# power-module.net
KiCad netlist of a schematic drawn in EAGLE
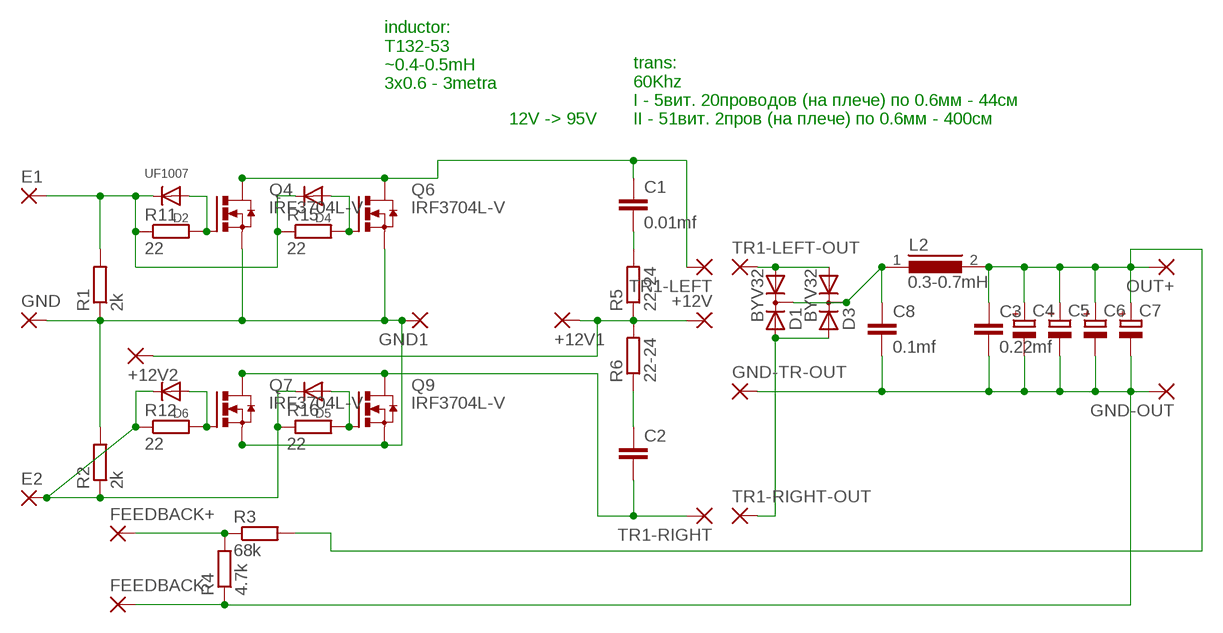
[diagram p0: schematic, sheet 1]

(export (version "E")
  (design (tool "Eeschema 10.0.6"))
  (components
    (comp (ref "+12V")
      (value "3,81/1,1")
      (footprint "eagle-import:3,81_1,1")
      (libsource (lib "eagle-import") (part "3,81/1,1"))
    )
    (comp (ref "+12V1")
      (value "3,81/1,1")
      (footprint "eagle-import:3,81_1,1")
      (libsource (lib "eagle-import") (part "3,81/1,1"))
    )
    (comp (ref "+12V2")
      (value "3,81/1,1")
      (footprint "eagle-import:3,81_1,1")
      (libsource (lib "eagle-import") (part "3,81/1,1"))
    )
    (comp (ref "C1")
      (value "0.01mf")
      (footprint "eagle-import:C102-064X133")
      (libsource (lib "eagle-import") (part "C-EU102-064X133"))
    )
    (comp (ref "C2")
      (value "C-EU102-064X133")
      (footprint "eagle-import:C102-064X133")
      (libsource (lib "eagle-import") (part "C-EU102-064X133"))
    )
    (comp (ref "C3")
      (value "0.22mf")
      (footprint "eagle-import:C150-064X183")
      (libsource (lib "eagle-import") (part "C-EU150-064X183"))
    )
    (comp (ref "C4")
      (value "CPOL-EUE10-22.5")
      (footprint "eagle-import:EB22,5D")
      (libsource (lib "eagle-import") (part "CPOL-EUE10-22.5"))
    )
    (comp (ref "C5")
      (value "CPOL-EUE10-22.5")
      (footprint "eagle-import:EB22,5D")
      (libsource (lib "eagle-import") (part "CPOL-EUE10-22.5"))
    )
    (comp (ref "C6")
      (value "CPOL-EUE10-22.5")
      (footprint "eagle-import:EB22,5D")
      (libsource (lib "eagle-import") (part "CPOL-EUE10-22.5"))
    )
    (comp (ref "C7")
      (value "CPOL-EUE10-22.5")
      (footprint "eagle-import:EB22,5D")
      (libsource (lib "eagle-import") (part "CPOL-EUE10-22.5"))
    )
    (comp (ref "C8")
      (value "0.1mf")
      (footprint "eagle-import:C150-064X183")
      (libsource (lib "eagle-import") (part "C-EU150-064X183"))
    )
    (comp (ref "D1")
      (value "BYV32")
      (footprint "eagle-import:TO220ABS")
      (libsource (lib "eagle-import") (part "BYV32"))
    )
    (comp (ref "D2")
      (value "UF1007")
      (footprint "eagle-import:DO-1N4148")
      (libsource (lib "eagle-import") (part "DIODEDO-1N4148"))
    )
    (comp (ref "D3")
      (value "BYV32")
      (footprint "eagle-import:TO220ABS")
      (libsource (lib "eagle-import") (part "BYV32"))
    )
    (comp (ref "D4")
      (value "DIODEDO-1N4148")
      (footprint "eagle-import:DO-1N4148")
      (libsource (lib "eagle-import") (part "DIODEDO-1N4148"))
    )
    (comp (ref "D5")
      (value "DIODEDO-1N4148")
      (footprint "eagle-import:DO-1N4148")
      (libsource (lib "eagle-import") (part "DIODEDO-1N4148"))
    )
    (comp (ref "D6")
      (value "DIODEDO-1N4148")
      (footprint "eagle-import:DO-1N4148")
      (libsource (lib "eagle-import") (part "DIODEDO-1N4148"))
    )
    (comp (ref "E1")
      (value "3,81/1,1")
      (footprint "eagle-import:3,81_1,1")
      (libsource (lib "eagle-import") (part "3,81/1,1"))
    )
    (comp (ref "E2")
      (value "3,81/1,1")
      (footprint "eagle-import:3,81_1,1")
      (libsource (lib "eagle-import") (part "3,81/1,1"))
    )
    (comp (ref "FEEDBACK+")
      (value "3,81/1,1")
      (footprint "eagle-import:3,81_1,1")
      (libsource (lib "eagle-import") (part "3,81/1,1"))
    )
    (comp (ref "FEEDBACK-")
      (value "3,81/1,1")
      (footprint "eagle-import:3,81_1,1")
      (libsource (lib "eagle-import") (part "3,81/1,1"))
    )
    (comp (ref "GND")
      (value "3,81/1,1")
      (footprint "eagle-import:3,81_1,1")
      (libsource (lib "eagle-import") (part "3,81/1,1"))
    )
    (comp (ref "GND-OUT")
      (value "3,81/1,1")
      (footprint "eagle-import:3,81_1,1")
      (libsource (lib "eagle-import") (part "3,81/1,1"))
    )
    (comp (ref "GND-TR-OUT")
      (value "3,81/1,1")
      (footprint "eagle-import:3,81_1,1")
      (libsource (lib "eagle-import") (part "3,81/1,1"))
    )
    (comp (ref "GND1")
      (value "3,81/1,1")
      (footprint "eagle-import:3,81_1,1")
      (libsource (lib "eagle-import") (part "3,81/1,1"))
    )
    (comp (ref "L2")
      (value "0.3-0.7mH")
      (footprint "eagle-import:11-27")
      (libsource (lib "eagle-import") (part "R2711F11"))
    )
    (comp (ref "OUT+")
      (value "3,81/1,1")
      (footprint "eagle-import:3,81_1,1")
      (libsource (lib "eagle-import") (part "3,81/1,1"))
    )
    (comp (ref "Q4")
      (value "IRF3704L-V")
      (footprint "eagle-import:TO262-V")
      (libsource (lib "eagle-import") (part "IRF3704L-V"))
    )
    (comp (ref "Q6")
      (value "IRF3704L-V")
      (footprint "eagle-import:TO262-V")
      (libsource (lib "eagle-import") (part "IRF3704L-V"))
    )
    (comp (ref "Q7")
      (value "IRF3704L-V")
      (footprint "eagle-import:TO262-V")
      (libsource (lib "eagle-import") (part "IRF3704L-V"))
    )
    (comp (ref "Q9")
      (value "IRF3704L-V")
      (footprint "eagle-import:TO262-V")
      (libsource (lib "eagle-import") (part "IRF3704L-V"))
    )
    (comp (ref "R1")
      (value "2k")
      (footprint "eagle-import:0204_7")
      (libsource (lib "eagle-import") (part "R-EU_0204/7"))
    )
    (comp (ref "R2")
      (value "2k")
      (footprint "eagle-import:0204_7")
      (libsource (lib "eagle-import") (part "R-EU_0204/7"))
    )
    (comp (ref "R3")
      (value "68k")
      (footprint "eagle-import:0617_17")
      (libsource (lib "eagle-import") (part "R-EU_0617/17"))
    )
    (comp (ref "R4")
      (value "4.7k")
      (footprint "eagle-import:0617_17")
      (libsource (lib "eagle-import") (part "R-EU_0617/17"))
    )
    (comp (ref "R5")
      (value "22-24")
      (footprint "eagle-import:P0613_15")
      (libsource (lib "eagle-import") (part "R-EU_0613/15"))
    )
    (comp (ref "R6")
      (value "22-24")
      (footprint "eagle-import:P0613_15")
      (libsource (lib "eagle-import") (part "R-EU_0613/15"))
    )
    (comp (ref "R11")
      (value "22")
      (footprint "eagle-import:0204_7")
      (libsource (lib "eagle-import") (part "R-EU_0204/7"))
    )
    (comp (ref "R12")
      (value "22")
      (footprint "eagle-import:0204_7")
      (libsource (lib "eagle-import") (part "R-EU_0204/7"))
    )
    (comp (ref "R15")
      (value "22")
      (footprint "eagle-import:0204_7")
      (libsource (lib "eagle-import") (part "R-EU_0204/7"))
    )
    (comp (ref "R16")
      (value "22")
      (footprint "eagle-import:0204_7")
      (libsource (lib "eagle-import") (part "R-EU_0204/7"))
    )
    (comp (ref "TR1-LEFT")
      (value "3,81/1,1")
      (footprint "eagle-import:3,81_1,1")
      (libsource (lib "eagle-import") (part "3,81/1,1"))
    )
    (comp (ref "TR1-LEFT-OUT")
      (value "3,81/1,1")
      (footprint "eagle-import:3,81_1,1")
      (libsource (lib "eagle-import") (part "3,81/1,1"))
    )
    (comp (ref "TR1-RIGHT")
      (value "3,81/1,1")
      (footprint "eagle-import:3,81_1,1")
      (libsource (lib "eagle-import") (part "3,81/1,1"))
    )
    (comp (ref "TR1-RIGHT-OUT")
      (value "3,81/1,1")
      (footprint "eagle-import:3,81_1,1")
      (libsource (lib "eagle-import") (part "3,81/1,1"))
    )
  )
  (nets
    (net (code "1") (name "Net-(+12V-P)") (class "Default")
      (node (ref "+12V") (pin "1") (pinfunction "P_1") (pintype "passive"))
      (node (ref "+12V1") (pin "1") (pinfunction "P_1") (pintype "passive"))
      (node (ref "+12V2") (pin "1") (pinfunction "P_1") (pintype "passive"))
      (node (ref "R5") (pin "1") (pinfunction "1_1") (pintype "passive"))
      (node (ref "R6") (pin "2") (pinfunction "2_2") (pintype "passive"))
    )
    (net (code "2") (name "Net-(C1-Pad2)") (class "Default")
      (node (ref "C1") (pin "2") (pinfunction "2_2") (pintype "passive"))
      (node (ref "R5") (pin "2") (pinfunction "2_2") (pintype "passive"))
    )
    (net (code "3") (name "Net-(C2-Pad1)") (class "Default")
      (node (ref "C2") (pin "1") (pinfunction "1_1") (pintype "passive"))
      (node (ref "R6") (pin "1") (pinfunction "1_1") (pintype "passive"))
    )
    (net (code "4") (name "Net-(C8-Pad1)") (class "Default")
      (node (ref "C8") (pin "1") (pinfunction "1_1") (pintype "passive"))
      (node (ref "D1") (pin "C") (pinfunction "C_C") (pintype "passive"))
      (node (ref "D3") (pin "C") (pinfunction "C_C") (pintype "passive"))
      (node (ref "L2") (pin "1") (pinfunction "1_1") (pintype "passive"))
    )
    (net (code "5") (name "Net-(E1-P)") (class "Default")
      (node (ref "D2") (pin "C") (pinfunction "C_C") (pintype "passive"))
      (node (ref "D4") (pin "C") (pinfunction "C_C") (pintype "passive"))
      (node (ref "E1") (pin "1") (pinfunction "P_1") (pintype "passive"))
      (node (ref "R1") (pin "2") (pinfunction "2_2") (pintype "passive"))
      (node (ref "R11") (pin "1") (pinfunction "1_1") (pintype "passive"))
      (node (ref "R15") (pin "1") (pinfunction "1_1") (pintype "passive"))
    )
    (net (code "6") (name "Net-(E2-P)") (class "Default")
      (node (ref "D5") (pin "C") (pinfunction "C_C") (pintype "passive"))
      (node (ref "D6") (pin "C") (pinfunction "C_C") (pintype "passive"))
      (node (ref "E2") (pin "1") (pinfunction "P_1") (pintype "passive"))
      (node (ref "R12") (pin "1") (pinfunction "1_1") (pintype "passive"))
      (node (ref "R16") (pin "1") (pinfunction "1_1") (pintype "passive"))
      (node (ref "R2") (pin "1") (pinfunction "1_1") (pintype "passive"))
    )
    (net (code "7") (name "Net-(FEEDBACK+-P)") (class "Default")
      (node (ref "FEEDBACK+") (pin "1") (pinfunction "P_1") (pintype "passive"))
      (node (ref "R3") (pin "1") (pinfunction "1_1") (pintype "passive"))
      (node (ref "R4") (pin "2") (pinfunction "2_2") (pintype "passive"))
    )
    (net (code "8") (name "Net-(FEEDBACK--P)") (class "Default")
      (node (ref "C3") (pin "2") (pinfunction "2_2") (pintype "passive"))
      (node (ref "C4") (pin "-") (pinfunction "-_-") (pintype "passive"))
      (node (ref "C5") (pin "-") (pinfunction "-_-") (pintype "passive"))
      (node (ref "C6") (pin "-") (pinfunction "-_-") (pintype "passive"))
      (node (ref "C7") (pin "-") (pinfunction "-_-") (pintype "passive"))
      (node (ref "C8") (pin "2") (pinfunction "2_2") (pintype "passive"))
      (node (ref "FEEDBACK-") (pin "1") (pinfunction "P_1") (pintype "passive"))
      (node (ref "GND-OUT") (pin "1") (pinfunction "P_1") (pintype "passive"))
      (node (ref "GND-TR-OUT") (pin "1") (pinfunction "P_1") (pintype "passive"))
      (node (ref "R4") (pin "1") (pinfunction "1_1") (pintype "passive"))
    )
    (net (code "9") (name "Net-(GND-P)") (class "Default")
      (node (ref "GND") (pin "1") (pinfunction "P_1") (pintype "passive"))
      (node (ref "GND1") (pin "1") (pinfunction "P_1") (pintype "passive"))
      (node (ref "Q4") (pin "3") (pinfunction "S_3") (pintype "passive"))
      (node (ref "Q6") (pin "3") (pinfunction "S_3") (pintype "passive"))
      (node (ref "Q7") (pin "3") (pinfunction "S_3") (pintype "passive"))
      (node (ref "Q9") (pin "3") (pinfunction "S_3") (pintype "passive"))
      (node (ref "R1") (pin "1") (pinfunction "1_1") (pintype "passive"))
      (node (ref "R2") (pin "2") (pinfunction "2_2") (pintype "passive"))
    )
    (net (code "10") (name "Net-(OUT+-P)") (class "Default")
      (node (ref "C3") (pin "1") (pinfunction "1_1") (pintype "passive"))
      (node (ref "C4") (pin "+") (pinfunction "+_+") (pintype "passive"))
      (node (ref "C5") (pin "+") (pinfunction "+_+") (pintype "passive"))
      (node (ref "C6") (pin "+") (pinfunction "+_+") (pintype "passive"))
      (node (ref "C7") (pin "+") (pinfunction "+_+") (pintype "passive"))
      (node (ref "L2") (pin "2") (pinfunction "2_2") (pintype "passive"))
      (node (ref "OUT+") (pin "1") (pinfunction "P_1") (pintype "passive"))
      (node (ref "R3") (pin "2") (pinfunction "2_2") (pintype "passive"))
    )
    (net (code "11") (name "Net-(Q4-D)") (class "Default")
      (node (ref "C1") (pin "1") (pinfunction "1_1") (pintype "passive"))
      (node (ref "Q4") (pin "2") (pinfunction "D_2") (pintype "passive"))
      (node (ref "Q6") (pin "2") (pinfunction "D_2") (pintype "passive"))
      (node (ref "TR1-LEFT") (pin "1") (pinfunction "P_1") (pintype "passive"))
    )
    (net (code "12") (name "Net-(Q4-G)") (class "Default")
      (node (ref "D2") (pin "A") (pinfunction "A_A") (pintype "passive"))
      (node (ref "Q4") (pin "1") (pinfunction "G_1") (pintype "passive"))
      (node (ref "R11") (pin "2") (pinfunction "2_2") (pintype "passive"))
    )
    (net (code "13") (name "Net-(Q6-G)") (class "Default")
      (node (ref "D4") (pin "A") (pinfunction "A_A") (pintype "passive"))
      (node (ref "Q6") (pin "1") (pinfunction "G_1") (pintype "passive"))
      (node (ref "R15") (pin "2") (pinfunction "2_2") (pintype "passive"))
    )
    (net (code "14") (name "Net-(Q7-D)") (class "Default")
      (node (ref "C2") (pin "2") (pinfunction "2_2") (pintype "passive"))
      (node (ref "Q7") (pin "2") (pinfunction "D_2") (pintype "passive"))
      (node (ref "Q9") (pin "2") (pinfunction "D_2") (pintype "passive"))
      (node (ref "TR1-RIGHT") (pin "1") (pinfunction "P_1") (pintype "passive"))
    )
    (net (code "15") (name "Net-(Q7-G)") (class "Default")
      (node (ref "D6") (pin "A") (pinfunction "A_A") (pintype "passive"))
      (node (ref "Q7") (pin "1") (pinfunction "G_1") (pintype "passive"))
      (node (ref "R12") (pin "2") (pinfunction "2_2") (pintype "passive"))
    )
    (net (code "16") (name "Net-(Q9-G)") (class "Default")
      (node (ref "D5") (pin "A") (pinfunction "A_A") (pintype "passive"))
      (node (ref "Q9") (pin "1") (pinfunction "G_1") (pintype "passive"))
      (node (ref "R16") (pin "2") (pinfunction "2_2") (pintype "passive"))
    )
    (net (code "17") (name "Net-(TR1-LEFT-OUT-P)") (class "Default")
      (node (ref "D1") (pin "A1") (pinfunction "A1_A1") (pintype "passive"))
      (node (ref "D3") (pin "A1") (pinfunction "A1_A1") (pintype "passive"))
      (node (ref "TR1-LEFT-OUT") (pin "1") (pinfunction "P_1") (pintype "passive"))
    )
    (net (code "18") (name "Net-(TR1-RIGHT-OUT-P)") (class "Default")
      (node (ref "D1") (pin "A2") (pinfunction "A2_A2") (pintype "passive"))
      (node (ref "D3") (pin "A2") (pinfunction "A2_A2") (pintype "passive"))
      (node (ref "TR1-RIGHT-OUT") (pin "1") (pinfunction "P_1") (pintype "passive"))
    )
  )
)
